# fig2.net
KiCad netlist of a schematic drawn in EasyEDA
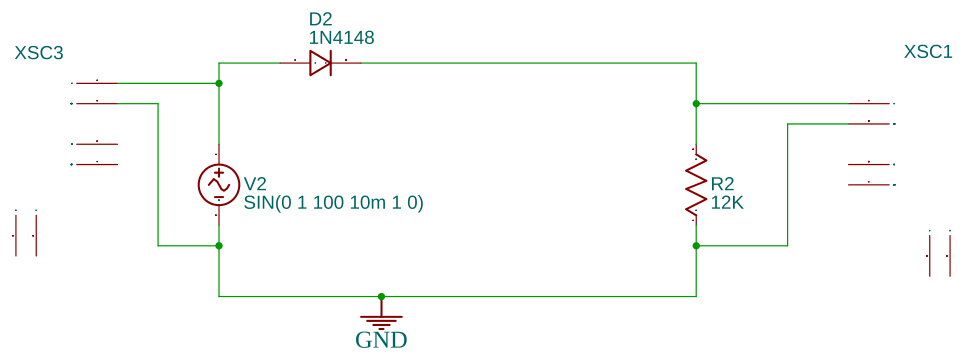
[diagram p0: schematic sheet]

(export (version "E")
  (design (tool "Eeschema 10.0.6"))
  (components
    (comp (ref "D2") (value "1N4148") (libsource (lib "") (part "1N4148")))
    (comp (ref "R2") (value "12K") (libsource (lib "") (part "Resistor_US")))
    (comp (ref "V2") (value "SIN(0 1 100 10m 1 0)") (libsource (lib "") (part "VSin")))
    (comp (ref "XSC1") (value "Oscilloscope") (libsource (lib "") (part "OSCILLOSCOPE_1")))
    (comp (ref "XSC3") (value "Oscilloscope") (libsource (lib "") (part "OSCILLOSCOPE")))
  )
  (nets
    (net (code "1") (name "GND") (class "Default")
      (node (ref "R2") (pin "1") (pinfunction "1_1") (pintype "unspecified"))
      (node (ref "V2") (pin "2") (pinfunction "2_2") (pintype "unspecified"))
      (node (ref "XSC1") (pin "2") (pinfunction "GND1_2") (pintype "unspecified"))
      (node (ref "XSC3") (pin "2") (pinfunction "GND1_2") (pintype "unspecified"))
    )
    (net (code "2") (name "Net-(D2-A)") (class "Default")
      (node (ref "D2") (pin "1") (pinfunction "A_1") (pintype "unspecified"))
      (node (ref "V2") (pin "1") (pinfunction "1_1") (pintype "unspecified"))
      (node (ref "XSC3") (pin "1") (pinfunction "A_1") (pintype "unspecified"))
    )
    (net (code "3") (name "Net-(D2-K)") (class "Default")
      (node (ref "D2") (pin "2") (pinfunction "K_2") (pintype "unspecified"))
      (node (ref "R2") (pin "2") (pinfunction "2_2") (pintype "unspecified"))
      (node (ref "XSC1") (pin "1") (pinfunction "A_1") (pintype "unspecified"))
    )
    (net (code "4") (name "unconnected-(XSC1-B-Pad3)") (class "Default")
      (node (ref "XSC1") (pin "3") (pinfunction "B_3") (pintype "unspecified"))
    )
    (net (code "5") (name "unconnected-(XSC1-GND2-Pad4)") (class "Default")
      (node (ref "XSC1") (pin "4") (pinfunction "GND2_4") (pintype "unspecified"))
    )
    (net (code "6") (name "unconnected-(XSC1-T+-Pad5)") (class "Default")
      (node (ref "XSC1") (pin "5") (pinfunction "T+_5") (pintype "unspecified"))
    )
    (net (code "7") (name "unconnected-(XSC1-T--Pad6)") (class "Default")
      (node (ref "XSC1") (pin "6") (pinfunction "T-_6") (pintype "unspecified"))
    )
    (net (code "8") (name "unconnected-(XSC3-B-Pad3)") (class "Default")
      (node (ref "XSC3") (pin "3") (pinfunction "B_3") (pintype "unspecified"))
    )
    (net (code "9") (name "unconnected-(XSC3-GND2-Pad4)") (class "Default")
      (node (ref "XSC3") (pin "4") (pinfunction "GND2_4") (pintype "unspecified"))
    )
    (net (code "10") (name "unconnected-(XSC3-T+-Pad5)") (class "Default")
      (node (ref "XSC3") (pin "5") (pinfunction "T+_5") (pintype "unspecified"))
    )
    (net (code "11") (name "unconnected-(XSC3-T--Pad6)") (class "Default")
      (node (ref "XSC3") (pin "6") (pinfunction "T-_6") (pintype "unspecified"))
    )
  )
)
